# FPGAGTP.net
KiCad netlist of a schematic drawn in Altium Designer
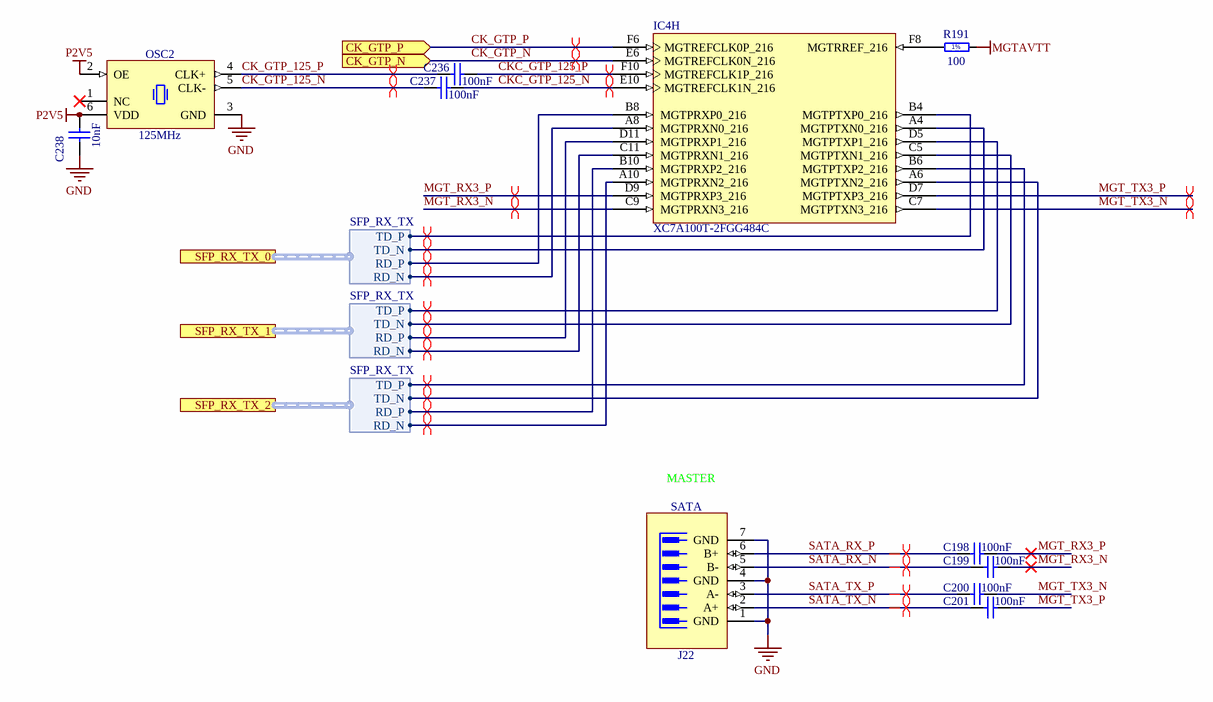
[diagram p0: FPGAGTP.SchDoc]

(export (version "E")
  (design (tool "Eeschema 10.0.6"))
  (components
    (comp (ref "C198")
      (value "100nF")
      (footprint "CAPC0603X33N")
      (description "Non-polarised capacitor")
      (fields
        (field (name "PART NUMBER") "CC0201_100NF_6.3V_10%_X5R")
        (field (name "VOLTAGE") "6.3V")
        (field (name "AUTHOR") "CERN DEM JLC")
      )
      (libsource (lib "Capacitors") (part "Capacitor - non polarized"))
    )
    (comp (ref "C199")
      (value "100nF")
      (footprint "CAPC0603X33N")
      (description "Non-polarised capacitor")
      (fields
        (field (name "PART NUMBER") "CC0201_100NF_6.3V_10%_X5R")
        (field (name "VOLTAGE") "6.3V")
        (field (name "AUTHOR") "CERN DEM JLC")
      )
      (libsource (lib "Capacitors") (part "Capacitor - non polarized"))
    )
    (comp (ref "C200")
      (value "100nF")
      (footprint "CAPC0603X33N")
      (description "Non-polarised capacitor")
      (fields
        (field (name "PART NUMBER") "CC0201_100NF_6.3V_10%_X5R")
        (field (name "VOLTAGE") "6.3V")
        (field (name "AUTHOR") "CERN DEM JLC")
      )
      (libsource (lib "Capacitors") (part "Capacitor - non polarized"))
    )
    (comp (ref "C201")
      (value "100nF")
      (footprint "CAPC0603X33N")
      (description "Non-polarised capacitor")
      (fields
        (field (name "PART NUMBER") "CC0201_100NF_6.3V_10%_X5R")
        (field (name "VOLTAGE") "6.3V")
        (field (name "AUTHOR") "CERN DEM JLC")
      )
      (libsource (lib "Capacitors") (part "Capacitor - non polarized"))
    )
    (comp (ref "C236")
      (value "100nF")
      (footprint "CAPC0603X33N")
      (description "Non-polarised capacitor")
      (fields
        (field (name "PART NUMBER") "CC0201_100NF_6.3V_10%_X5R")
        (field (name "VOLTAGE") "6.3V")
        (field (name "AUTHOR") "CERN DEM JLC")
      )
      (libsource (lib "Capacitors") (part "Capacitor - non polarized"))
    )
    (comp (ref "C237")
      (value "100nF")
      (footprint "CAPC0603X33N")
      (description "Non-polarised capacitor")
      (fields
        (field (name "PART NUMBER") "CC0201_100NF_6.3V_10%_X5R")
        (field (name "VOLTAGE") "6.3V")
        (field (name "AUTHOR") "CERN DEM JLC")
      )
      (libsource (lib "Capacitors") (part "Capacitor - non polarized"))
    )
    (comp (ref "C238")
      (value "10nF")
      (footprint "CAPC1005X55N")
      (description "Non-polarised capacitor")
      (fields
        (field (name "PART NUMBER") "CC0402_10NF_16V_10%_X7R")
        (field (name "VOLTAGE") "16V")
        (field (name "AUTHOR") "CERN DEM JLC")
      )
      (libsource (lib "Capacitors") (part "Capacitor - non polarized"))
    )
    (comp (ref "IC4")
      (value "XC7A100T-2FGG484C")
      (footprint "FGG484")
      (description "Artix-7 FPGA, 285 User I/Os, 4 GTP, 484-Ball BGA, Speed Grade 2, Commercial Grade, Pb-Free")
      (fields (field (name "GENERIC PART NUMBER") "XC7A100T") (field (name "MANUFACTURER") "Xilinx"))
      (libsource (lib "Altium Content Vault") (part "XC7A100T-2FGG484C"))
    )
    (comp (ref "J22")
      (value "SATA")
      (footprint "MOLEX_67800-5005")
      (description "7 Pin SATA Receptacle")
      (fields
        (field (name "PART NUMBER") "MOLEX_67800-5005")
        (field (name "MANUFACTURER") "MOLEX")
        (field (name "AUTHOR") "CERN DEM MR")
      )
      (libsource (lib "Connectors") (part "Connector SATA 7 Male"))
    )
    (comp (ref "OSC2")
      (value "125MHz")
      (footprint "OSC_SILICON-LAB_SI510-6N")
      (description "Crystal Oscillator 6 pins, Si510 (LVDS/LVPECL/HCSL/Dual CMOS)")
      (fields
        (field (name "PART NUMBER") "OSC_125MHZ_SILICON-LAB_510FBA125M000AAG")
        (field (name "MANUFACTURER") "SILICON LABS")
        (field (name "AUTHOR") "CERN DEM JMW")
      )
      (libsource (lib "ICs And Semiconductors") (part "Oscillator SILICON-LAB_Si510-6N"))
    )
    (comp (ref "R191")
      (value "100")
      (footprint "RESC1005X40N")
      (description "Resistor - 1%")
      (fields
        (field (name "PART NUMBER") "R0402_100R_1%_0.0625W_100PPM")
        (field (name "POWER") "0.0625W")
        (field (name "AUTHOR") "CERN DEM JLC")
      )
      (libsource (lib "Resistors") (part "Resistor - 1%"))
    )
  )
  (nets
    (net (code "2") (name "/CKC_GTP_125_N") (class "Default")
      (node (ref "C237") (pin "2") (pinfunction "2_2") (pintype "passive"))
      (node (ref "IC4") (pin "E10") (pinfunction "MGTREFCLK1N_216_E10") (pintype "input"))
    )
    (net (code "3") (name "/CKC_GTP_125_P") (class "Default")
      (node (ref "C236") (pin "2") (pinfunction "2_2") (pintype "passive"))
      (node (ref "IC4") (pin "F10") (pinfunction "MGTREFCLK1P_216_F10") (pintype "input"))
    )
    (net (code "4") (name "/CK_GTP_125_N") (class "Default")
      (node (ref "C237") (pin "1") (pinfunction "1_1") (pintype "passive"))
      (node (ref "OSC2") (pin "5") (pinfunction "CLK-_5") (pintype "output"))
    )
    (net (code "5") (name "/CK_GTP_125_P") (class "Default")
      (node (ref "C236") (pin "1") (pinfunction "1_1") (pintype "passive"))
      (node (ref "OSC2") (pin "4") (pinfunction "CLK+_4") (pintype "output"))
    )
    (net (code "6") (name "/CK_GTP_N") (class "Default")
      (node (ref "IC4") (pin "E6") (pinfunction "MGTREFCLK0N_216_E6") (pintype "input"))
    )
    (net (code "7") (name "/CK_GTP_P") (class "Default")
      (node (ref "IC4") (pin "F6") (pinfunction "MGTREFCLK0P_216_F6") (pintype "input"))
    )
    (net (code "8") (name "/MGT_RX3_N") (class "Default")
      (node (ref "C199") (pin "2") (pinfunction "2_2") (pintype "passive"))
      (node (ref "IC4") (pin "C9") (pinfunction "MGTPRXN3_216_C9") (pintype "input"))
    )
    (net (code "9") (name "/MGT_RX3_P") (class "Default")
      (node (ref "C198") (pin "2") (pinfunction "2_2") (pintype "passive"))
      (node (ref "IC4") (pin "D9") (pinfunction "MGTPRXP3_216_D9") (pintype "input"))
    )
    (net (code "10") (name "/MGT_TX3_N") (class "Default")
      (node (ref "C200") (pin "2") (pinfunction "2_2") (pintype "passive"))
      (node (ref "IC4") (pin "C7") (pinfunction "MGTPTXN3_216_C7") (pintype "output"))
    )
    (net (code "11") (name "/MGT_TX3_P") (class "Default")
      (node (ref "C201") (pin "2") (pinfunction "2_2") (pintype "passive"))
      (node (ref "IC4") (pin "D7") (pinfunction "MGTPTXP3_216_D7") (pintype "output"))
    )
    (net (code "12") (name "/SATA_RX_N") (class "Default")
      (node (ref "C199") (pin "1") (pinfunction "1_1") (pintype "passive"))
      (node (ref "J22") (pin "5") (pinfunction "B-_5") (pintype "bidirectional"))
    )
    (net (code "13") (name "/SATA_RX_P") (class "Default")
      (node (ref "C198") (pin "1") (pinfunction "1_1") (pintype "passive"))
      (node (ref "J22") (pin "6") (pinfunction "B+_6") (pintype "bidirectional"))
    )
    (net (code "14") (name "/SATA_TX_N") (class "Default")
      (node (ref "C201") (pin "1") (pinfunction "1_1") (pintype "passive"))
      (node (ref "J22") (pin "2") (pinfunction "A+_2") (pintype "bidirectional"))
    )
    (net (code "15") (name "/SATA_TX_P") (class "Default")
      (node (ref "C200") (pin "1") (pinfunction "1_1") (pintype "passive"))
      (node (ref "J22") (pin "3") (pinfunction "A-_3") (pintype "bidirectional"))
    )
    (net (code "17") (name "GND") (class "Default")
      (node (ref "C238") (pin "1") (pinfunction "1_1") (pintype "passive"))
      (node (ref "J22") (pin "1") (pinfunction "GND_1") (pintype "power_in"))
      (node (ref "J22") (pin "4") (pinfunction "GND_4") (pintype "power_in"))
      (node (ref "J22") (pin "7") (pinfunction "GND_7") (pintype "power_in"))
      (node (ref "OSC2") (pin "3") (pinfunction "GND_3") (pintype "power_in"))
    )
    (net (code "18") (name "MGTAVTT") (class "Default")
      (node (ref "R191") (pin "1") (pinfunction "1_1") (pintype "passive"))
    )
    (net (code "19") (name "Net-(IC4H-MGTRREF_216)") (class "Default")
      (node (ref "IC4") (pin "F8") (pinfunction "MGTRREF_216_F8") (pintype "input"))
      (node (ref "R191") (pin "2") (pinfunction "2_2") (pintype "passive"))
    )
    (net (code "20") (name "P2V5") (class "Default")
      (node (ref "C238") (pin "2") (pinfunction "2_2") (pintype "passive"))
      (node (ref "OSC2") (pin "2") (pinfunction "OE_2") (pintype "input"))
      (node (ref "OSC2") (pin "6") (pinfunction "VDD_6") (pintype "power_in"))
    )
    (net (code "21") (name "unconnected-(IC4H-MGTPRXN0_216-PadA8)") (class "Default")
      (node (ref "IC4") (pin "A8") (pinfunction "MGTPRXN0_216_A8") (pintype "input"))
    )
    (net (code "22") (name "unconnected-(IC4H-MGTPRXN1_216-PadC11)") (class "Default")
      (node (ref "IC4") (pin "C11") (pinfunction "MGTPRXN1_216_C11") (pintype "input"))
    )
    (net (code "23") (name "unconnected-(IC4H-MGTPRXN2_216-PadA10)") (class "Default")
      (node (ref "IC4") (pin "A10") (pinfunction "MGTPRXN2_216_A10") (pintype "input"))
    )
    (net (code "24") (name "unconnected-(IC4H-MGTPRXP0_216-PadB8)") (class "Default")
      (node (ref "IC4") (pin "B8") (pinfunction "MGTPRXP0_216_B8") (pintype "input"))
    )
    (net (code "25") (name "unconnected-(IC4H-MGTPRXP1_216-PadD11)") (class "Default")
      (node (ref "IC4") (pin "D11") (pinfunction "MGTPRXP1_216_D11") (pintype "input"))
    )
    (net (code "26") (name "unconnected-(IC4H-MGTPRXP2_216-PadB10)") (class "Default")
      (node (ref "IC4") (pin "B10") (pinfunction "MGTPRXP2_216_B10") (pintype "input"))
    )
    (net (code "27") (name "unconnected-(IC4H-MGTPTXN0_216-PadA4)") (class "Default")
      (node (ref "IC4") (pin "A4") (pinfunction "MGTPTXN0_216_A4") (pintype "output"))
    )
    (net (code "28") (name "unconnected-(IC4H-MGTPTXN1_216-PadC5)") (class "Default")
      (node (ref "IC4") (pin "C5") (pinfunction "MGTPTXN1_216_C5") (pintype "output"))
    )
    (net (code "29") (name "unconnected-(IC4H-MGTPTXN2_216-PadA6)") (class "Default")
      (node (ref "IC4") (pin "A6") (pinfunction "MGTPTXN2_216_A6") (pintype "output"))
    )
    (net (code "30") (name "unconnected-(IC4H-MGTPTXP0_216-PadB4)") (class "Default")
      (node (ref "IC4") (pin "B4") (pinfunction "MGTPTXP0_216_B4") (pintype "output"))
    )
    (net (code "31") (name "unconnected-(IC4H-MGTPTXP1_216-PadD5)") (class "Default")
      (node (ref "IC4") (pin "D5") (pinfunction "MGTPTXP1_216_D5") (pintype "output"))
    )
    (net (code "32") (name "unconnected-(IC4H-MGTPTXP2_216-PadB6)") (class "Default")
      (node (ref "IC4") (pin "B6") (pinfunction "MGTPTXP2_216_B6") (pintype "output"))
    )
    (net (code "33") (name "unconnected-(OSC2-NC-Pad1)") (class "Default")
      (node (ref "OSC2") (pin "1") (pinfunction "NC_1") (pintype "passive+no_connect"))
    )
  )
)
